# breakout.net
KiCad netlist of a schematic drawn in EAGLE
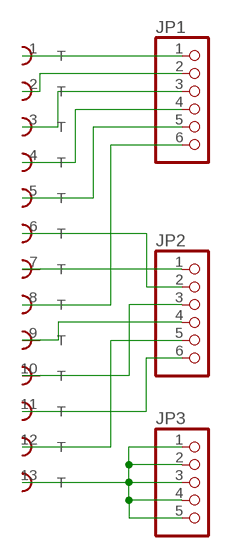
[diagram p0: schematic, sheet 1]

(export (version "E")
  (design (tool "Eeschema 10.0.6"))
  (components
    (comp (ref "J1")
      (value "DIN13T")
      (footprint "eagle-import:ADADS")
      (libsource (lib "eagle-import") (part "DIN13T"))
    )
    (comp (ref "JP1")
      (value "PINHD-1X6")
      (footprint "eagle-import:1X06")
      (libsource (lib "eagle-import") (part "PINHD-1X6"))
    )
    (comp (ref "JP2")
      (value "PINHD-1X6")
      (footprint "eagle-import:1X06")
      (libsource (lib "eagle-import") (part "PINHD-1X6"))
    )
    (comp (ref "JP3")
      (value "PINHD-1X5")
      (footprint "eagle-import:1X05")
      (libsource (lib "eagle-import") (part "PINHD-1X5"))
    )
  )
  (nets
    (net (code "1") (name "Net-(J1A-T)") (class "Default")
      (node (ref "J1") (pin "1") (pinfunction "T_1") (pintype "passive"))
      (node (ref "JP1") (pin "1") (pinfunction "1_1") (pintype "passive"))
    )
    (net (code "2") (name "Net-(J1B-T)") (class "Default")
      (node (ref "J1") (pin "10") (pinfunction "T_10") (pintype "passive"))
      (node (ref "JP2") (pin "3") (pinfunction "3_3") (pintype "passive"))
    )
    (net (code "3") (name "Net-(J1C-T)") (class "Default")
      (node (ref "J1") (pin "11") (pinfunction "T_11") (pintype "passive"))
      (node (ref "JP2") (pin "6") (pinfunction "6_6") (pintype "passive"))
    )
    (net (code "4") (name "Net-(J1D-T)") (class "Default")
      (node (ref "J1") (pin "12") (pinfunction "T_12") (pintype "passive"))
      (node (ref "JP2") (pin "5") (pinfunction "5_5") (pintype "passive"))
    )
    (net (code "5") (name "Net-(J1E-T)") (class "Default")
      (node (ref "J1") (pin "13") (pinfunction "T_13") (pintype "passive"))
      (node (ref "JP3") (pin "1") (pinfunction "1_1") (pintype "passive"))
      (node (ref "JP3") (pin "2") (pinfunction "2_2") (pintype "passive"))
      (node (ref "JP3") (pin "3") (pinfunction "3_3") (pintype "passive"))
      (node (ref "JP3") (pin "4") (pinfunction "4_4") (pintype "passive"))
      (node (ref "JP3") (pin "5") (pinfunction "5_5") (pintype "passive"))
    )
    (net (code "6") (name "Net-(J1F-T)") (class "Default")
      (node (ref "J1") (pin "2") (pinfunction "T_2") (pintype "passive"))
      (node (ref "JP1") (pin "2") (pinfunction "2_2") (pintype "passive"))
    )
    (net (code "7") (name "Net-(J1G-T)") (class "Default")
      (node (ref "J1") (pin "3") (pinfunction "T_3") (pintype "passive"))
      (node (ref "JP1") (pin "3") (pinfunction "3_3") (pintype "passive"))
    )
    (net (code "8") (name "Net-(J1H-T)") (class "Default")
      (node (ref "J1") (pin "4") (pinfunction "T_4") (pintype "passive"))
      (node (ref "JP1") (pin "4") (pinfunction "4_4") (pintype "passive"))
    )
    (net (code "9") (name "Net-(J1I-T)") (class "Default")
      (node (ref "J1") (pin "5") (pinfunction "T_5") (pintype "passive"))
      (node (ref "JP1") (pin "5") (pinfunction "5_5") (pintype "passive"))
    )
    (net (code "10") (name "Net-(J1J-T)") (class "Default")
      (node (ref "J1") (pin "6") (pinfunction "T_6") (pintype "passive"))
      (node (ref "JP2") (pin "2") (pinfunction "2_2") (pintype "passive"))
    )
    (net (code "11") (name "Net-(J1K-T)") (class "Default")
      (node (ref "J1") (pin "7") (pinfunction "T_7") (pintype "passive"))
      (node (ref "JP2") (pin "1") (pinfunction "1_1") (pintype "passive"))
    )
    (net (code "12") (name "Net-(J1L-T)") (class "Default")
      (node (ref "J1") (pin "8") (pinfunction "T_8") (pintype "passive"))
      (node (ref "JP1") (pin "6") (pinfunction "6_6") (pintype "passive"))
    )
    (net (code "13") (name "Net-(J1M-T)") (class "Default")
      (node (ref "J1") (pin "9") (pinfunction "T_9") (pintype "passive"))
      (node (ref "JP2") (pin "4") (pinfunction "4_4") (pintype "passive"))
    )
  )
)
